# Program_Debug-Interface.net
KiCad netlist of a schematic drawn in Altium Designer
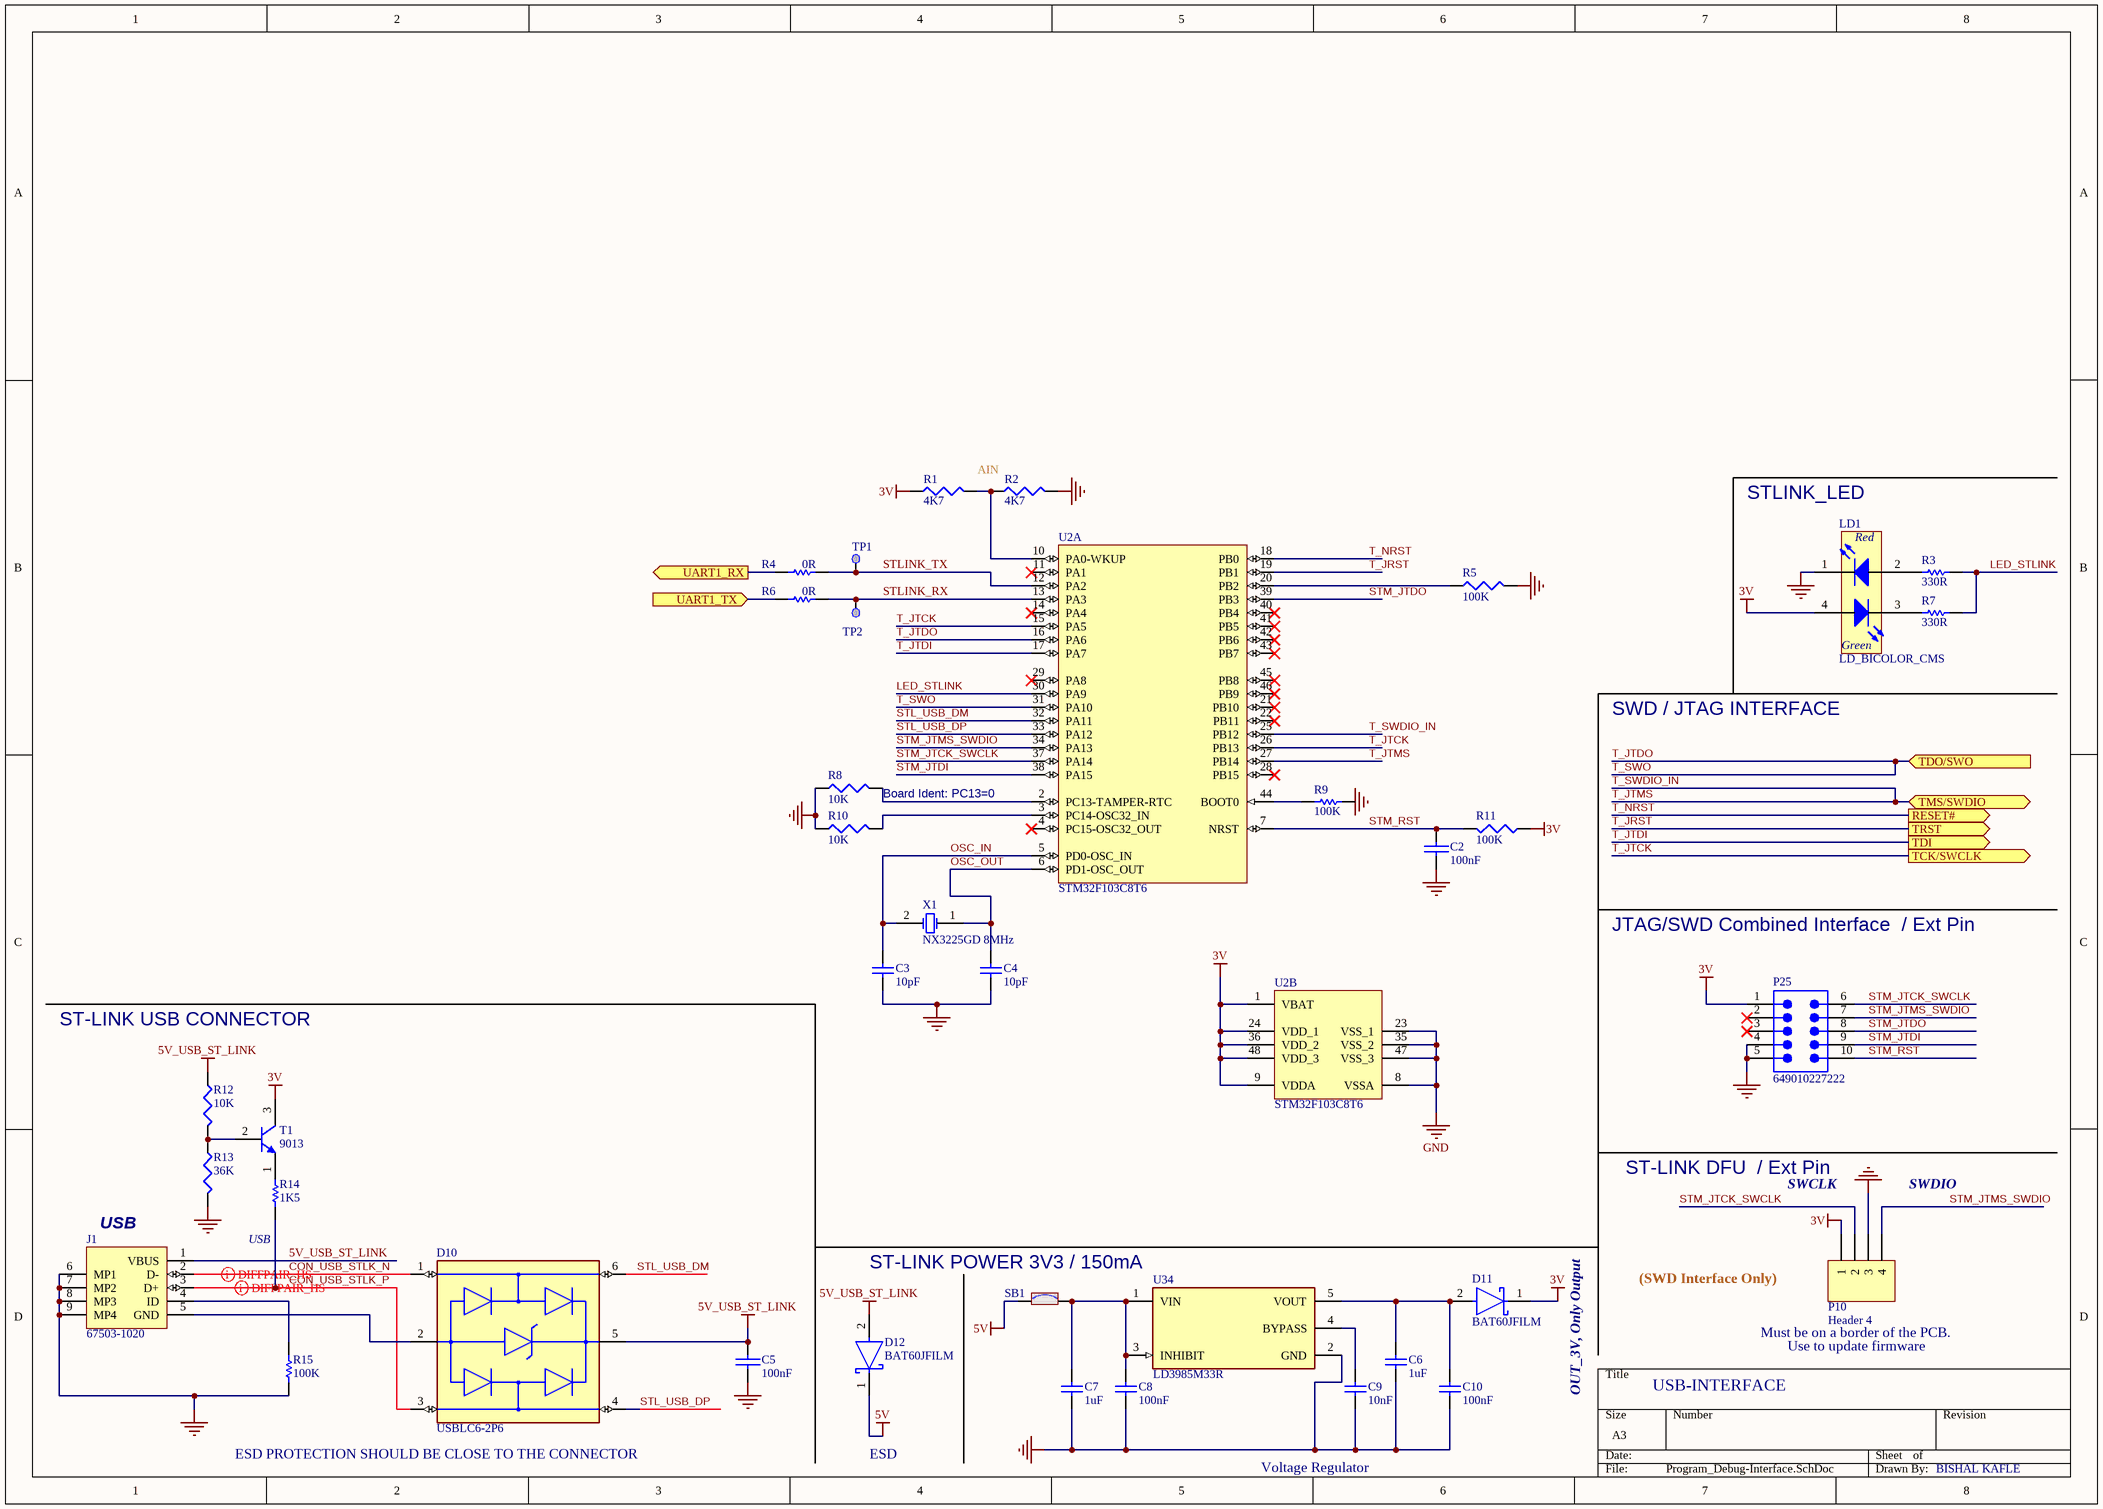
[diagram p0: Program_Debug-Interface.SchDoc]

(export (version "E")
  (design (tool "Eeschema 10.0.6"))
  (components
    (comp (ref "C2") (value "100nF") (footprint "0603C") (libsource (lib "") (part "CAP_1")))
    (comp (ref "C3")
      (value "10pF")
      (footprint "C0402")
      (description "Capacitor,10pF,50V,NPO,5%,0402")
      (fields
        (field (name "INTERNAL_PART_NUMBER") "MCD-00015")
        (field (name "MANUFACTURER_PART_NUMBER") "CC0402JRNPO9BN100")
        (field (name "PROVIDED_BY") "SUBCO")
      )
      (libsource (lib "MCD_PARTS_database") (part "Capacitor"))
    )
    (comp (ref "C4")
      (value "10pF")
      (footprint "C0402")
      (description "Capacitor,10pF,50V,NPO,5%,0402")
      (fields
        (field (name "INTERNAL_PART_NUMBER") "MCD-00015")
        (field (name "MANUFACTURER_PART_NUMBER") "CC0402JRNPO9BN100")
        (field (name "PROVIDED_BY") "SUBCO")
      )
      (libsource (lib "MCD_PARTS_database") (part "Capacitor"))
    )
    (comp (ref "C5")
      (value "100nF")
      (footprint "0603C")
      (description "Capacitor")
      (libsource (lib "*") (part "CAP"))
    )
    (comp (ref "C6")
      (value "1uF")
      (footprint "C0603")
      (description "Capacitor,1uF,6V3,X5R,10%,0603")
      (fields
        (field (name "INTERNAL_PART_NUMBER") "MCD-00238")
        (field (name "MANUFACTURER_PART_NUMBER") "CC0603KRX5R5BB105")
        (field (name "PROVIDED_BY") "SUBCO")
      )
      (libsource (lib "MCD_PARTS_database") (part "Capacitor"))
    )
    (comp (ref "C7")
      (value "1uF")
      (footprint "C0603")
      (description "Capacitor,1uF,6V3,X5R,10%,0603")
      (fields
        (field (name "INTERNAL_PART_NUMBER") "MCD-00238")
        (field (name "MANUFACTURER_PART_NUMBER") "CC0603KRX5R5BB105")
        (field (name "PROVIDED_BY") "SUBCO")
      )
      (libsource (lib "MCD_PARTS_database") (part "Capacitor"))
    )
    (comp (ref "C8")
      (value "100nF")
      (footprint "C0402")
      (description "Capacitor,100nF,16V,X7R,10%,0402")
      (fields
        (field (name "INTERNAL_PART_NUMBER") "MCD-00006")
        (field (name "MANUFACTURER_PART_NUMBER") "CC0402KRX7R7BB104")
        (field (name "PROVIDED_BY") "SUBCO")
      )
      (libsource (lib "MCD_PARTS_database") (part "Capacitor"))
    )
    (comp (ref "C9")
      (value "10nF")
      (footprint "C0402")
      (description "Capacitor,10nF,16V,X7R,10%,0402")
      (fields
        (field (name "INTERNAL_PART_NUMBER") "MCD-00011")
        (field (name "MANUFACTURER_PART_NUMBER") "CC0402KRX7R7BB103")
        (field (name "PROVIDED_BY") "SUBCO")
      )
      (libsource (lib "MCD_PARTS_database") (part "Capacitor"))
    )
    (comp (ref "C10")
      (value "100nF")
      (footprint "C0402")
      (description "Capacitor,100nF,16V,X7R,10%,0402")
      (fields
        (field (name "INTERNAL_PART_NUMBER") "MCD-00006")
        (field (name "MANUFACTURER_PART_NUMBER") "CC0402KRX7R7BB104")
        (field (name "PROVIDED_BY") "SUBCO")
      )
      (libsource (lib "MCD_PARTS_database") (part "Capacitor"))
    )
    (comp (ref "D10")
      (value "USBLC6-2P6")
      (footprint "FP-SOT-666-MFG")
      (description "TVS DIODE 5.25V 17V SOT666")
      (libsource (lib "Altium Content Vault") (part "c871e55f7e3243d341edbd671b98d92"))
    )
    (comp (ref "D11")
      (value "BAT60JFILM")
      (footprint "FP-BAT60JFILM-MFG")
      (description "DIODE SCHOTTKY 10V 3A SOD323")
      (libsource (lib "Altium Content Vault") (part "fefb30dabb5d097ae2f038500735429"))
    )
    (comp (ref "D12")
      (value "BAT60JFILM")
      (footprint "FP-BAT60JFILM-MFG")
      (description "DIODE SCHOTTKY 10V 3A SOD323")
      (libsource (lib "Altium Content Vault") (part "fefb30dabb5d097ae2f038500735429"))
    )
    (comp (ref "J1")
      (value "67503-1020")
      (footprint "MOLX-67503-1020_V")
      (description "USB, MINI, SMD, RA KME04-USBMU03A01")
      (fields (field (name "MANUFACTURER") "Molex"))
      (libsource (lib "esd_library") (part "MOLX-67503-1020"))
    )
    (comp (ref "LD1")
      (value "LD_BICOLOR_CMS")
      (footprint "LED_BI-GR_HSMF-A201-A00J1")
      (description "LED Bicolor")
      (fields
        (field (name "INTERNAL_PART_NUMBER") "MCD-00051")
        (field (name "MANUFACTURER_PART_NUMBER") "HSMF-A201-A00J1")
        (field (name "PROVIDED_BY") "SUBCO")
      )
      (libsource (lib "MCD_PARTS_database") (part "LD_BICOLOR_CMS"))
    )
    (comp (ref "P10")
      (value "Header 4")
      (footprint "HDR1X4")
      (description "Header, 4-Pin Male")
      (fields (field (name "MPN") "PEC04SFAN"))
      (libsource (lib "esd_library") (part "Header 4"))
    )
    (comp (ref "P25")
      (value "649010227222")
      (footprint "649010227222")
      (libsource (lib "Altium Content Vault") (part "Header_Male_2R_10P(A)"))
    )
    (comp (ref "R1") (value "4K7") (footprint "0603R") (libsource (lib "*") (part "RES1")))
    (comp (ref "R2") (value "4K7") (footprint "0603R") (libsource (lib "*") (part "RES1")))
    (comp (ref "R3")
      (value "330R")
      (footprint "R0402")
      (description "Resistor,330R,0402,1%,1/16W")
      (fields
        (field (name "INTERNAL_PART_NUMBER") "MCD-00062")
        (field (name "MANUFACTURER_PART_NUMBER") "RC0402FR-07330RL")
        (field (name "PROVIDED_BY") "SUBCO")
      )
      (libsource (lib "MCD_PARTS_database") (part "Resistor"))
    )
    (comp (ref "R4")
      (value "0R")
      (footprint "R0402")
      (description "Resistor,0R,0402,5%,1/16W")
      (fields
        (field (name "INTERNAL_PART_NUMBER") "MCD-00052")
        (field (name "MANUFACTURER_PART_NUMBER") "RC0402JR-070RL")
        (field (name "PROVIDED_BY") "SUBCO")
      )
      (libsource (lib "MCD_PARTS_database") (part "Resistor"))
    )
    (comp (ref "R5") (value "100K") (footprint "0603R") (libsource (lib "*") (part "RES1")))
    (comp (ref "R6")
      (value "0R")
      (footprint "R0402")
      (description "Resistor,0R,0402,5%,1/16W")
      (fields
        (field (name "INTERNAL_PART_NUMBER") "MCD-00052")
        (field (name "MANUFACTURER_PART_NUMBER") "RC0402JR-070RL")
        (field (name "PROVIDED_BY") "SUBCO")
      )
      (libsource (lib "MCD_PARTS_database") (part "Resistor"))
    )
    (comp (ref "R7")
      (value "330R")
      (footprint "R0402")
      (description "Resistor,330R,0402,1%,1/16W")
      (fields
        (field (name "INTERNAL_PART_NUMBER") "MCD-00062")
        (field (name "MANUFACTURER_PART_NUMBER") "RC0402FR-07330RL")
        (field (name "PROVIDED_BY") "SUBCO")
      )
      (libsource (lib "MCD_PARTS_database") (part "Resistor"))
    )
    (comp (ref "R8") (value "10K") (footprint "0603R") (libsource (lib "*") (part "R")))
    (comp (ref "R9")
      (value "100K")
      (footprint "R0402")
      (description "Resistor,100K,0402,1%,1/16W")
      (fields
        (field (name "INTERNAL_PART_NUMBER") "MCD-00059")
        (field (name "MANUFACTURER_PART_NUMBER") "RC0402FR-07100KL")
        (field (name "PROVIDED_BY") "SUBCO")
      )
      (libsource (lib "MCD_PARTS_database") (part "Resistor"))
    )
    (comp (ref "R10") (value "10K") (footprint "0603R") (libsource (lib "*") (part "R")))
    (comp (ref "R11") (value "100K") (footprint "0603R") (libsource (lib "*") (part "RES1")))
    (comp (ref "R12") (value "10K") (footprint "0603R") (libsource (lib "*") (part "R")))
    (comp (ref "R13") (value "36K") (footprint "0603R") (libsource (lib "*") (part "R")))
    (comp (ref "R14")
      (value "1K5")
      (footprint "0603R")
      (description "Resistor")
      (fields (field (name "PUBLISHER") "Altium Limited"))
      (libsource (lib "Miscellaneous Devices") (part "Res1"))
    )
    (comp (ref "R15")
      (value "100K")
      (footprint "R0402")
      (description "Resistor,100K,0402,1%,1/16W")
      (fields
        (field (name "INTERNAL_PART_NUMBER") "MCD-00059")
        (field (name "MANUFACTURER_PART_NUMBER") "RC0402FR-07100KL")
        (field (name "PROVIDED_BY") "SUBCO")
      )
      (libsource (lib "MCD_PARTS_database") (part "Resistor"))
    )
    (comp (ref "SB1")
      (value "~")
      (footprint "SOLDER-BRIDGE_R0603-0R")
      (description "Solder Bridge ON")
      (fields
        (field (name "INTERNAL_PART_NUMBER") "MCD-00071")
        (field (name "MANUFACTURER") "YAGEO")
        (field (name "PROVIDED_BY") "SUBCO")
      )
      (libsource (lib "MCD_PARTS_database") (part "SB_ON"))
    )
    (comp (ref "T1")
      (value "9013")
      (footprint "SOT23-213")
      (description "NPN Bipolar Transistor")
      (fields (field (name "PUBLISHER") "Altium Limited"))
      (libsource (lib "mb1045") (part "NPN"))
    )
    (comp (ref "TP1")
      (value "Test Point")
      (footprint "TP_SMD_1MM")
      (description "Test Point 1mm")
      (fields
        (field (name "INTERNAL_PART_NUMBER") "MCD-00074")
        (field (name "MANUFACTURER_PART_NUMBER") "n/a")
      )
      (libsource (lib "MCD_PARTS_database") (part "Test Point"))
    )
    (comp (ref "TP2")
      (value "Test Point")
      (footprint "TP_SMD_1MM")
      (description "Test Point 1mm")
      (fields
        (field (name "INTERNAL_PART_NUMBER") "MCD-00074")
        (field (name "MANUFACTURER_PART_NUMBER") "n/a")
      )
      (libsource (lib "") (part "Test Point_1"))
    )
    (comp (ref "U2")
      (value "STM32F103C8T6")
      (footprint "STM-LQFP48_L")
      (libsource (lib "Altium Content Vault") (part "MC-ARM-STM32F103X8_B-SQ48"))
    )
    (comp (ref "U34")
      (value "LD3985M33R")
      (footprint "FP-SOT23-5L-7049676-MFG")
      (libsource (lib "Altium Content Vault") (part "aba04f4e281572ab958dbcc456c8333"))
    )
    (comp (ref "X1")
      (value "NX3225GD 8MHz")
      (footprint "CRY_NX3225GD_2P")
      (description "Crystal 8Mhz, 8pF, -+50PPM, SMD")
      (fields
        (field (name "INTERNAL_PART_NUMBER") "MCD-00092")
        (field (name "MANUFACTURER_PART_NUMBER") "NX3225GD 8MHz EXS00A-CG04874")
        (field (name "PROVIDED_BY") "SUBCO")
      )
      (libsource (lib "MCD_PARTS_database") (part "XTAL_8M_NX3225GD"))
    )
  )
  (nets
    (net (code "1") (name "/CON_USB_STLK_N") (class "Default")
      (node (ref "D10") (pin "1") (pinfunction "I/O1_1") (pintype "bidirectional"))
      (node (ref "J1") (pin "2") (pinfunction "D-_2") (pintype "bidirectional"))
    )
    (net (code "2") (name "/CON_USB_STLK_P") (class "Default")
      (node (ref "D10") (pin "3") (pinfunction "I/O2_3") (pintype "bidirectional"))
      (node (ref "J1") (pin "3") (pinfunction "D+_3") (pintype "bidirectional"))
      (node (ref "R14") (pin "2") (pinfunction "2_2") (pintype "passive"))
    )
    (net (code "3") (name "/LED_STLINK") (class "Default")
      (node (ref "R3") (pin "2") (pinfunction "2_2") (pintype "passive"))
      (node (ref "R7") (pin "2") (pinfunction "2_2") (pintype "passive"))
      (node (ref "U2") (pin "30") (pinfunction "PA9_30") (pintype "bidirectional"))
    )
    (net (code "4") (name "/OSC_IN") (class "Default")
      (node (ref "C3") (pin "1") (pinfunction "1_1") (pintype "passive"))
      (node (ref "U2") (pin "5") (pinfunction "PD0-OSC_IN_5") (pintype "bidirectional"))
      (node (ref "X1") (pin "2") (pinfunction "OSC2_2") (pintype "passive"))
    )
    (net (code "5") (name "/OSC_OUT") (class "Default")
      (node (ref "C4") (pin "1") (pinfunction "1_1") (pintype "passive"))
      (node (ref "U2") (pin "6") (pinfunction "PD1-OSC_OUT_6") (pintype "bidirectional"))
      (node (ref "X1") (pin "1") (pinfunction "OSC1_1") (pintype "passive"))
    )
    (net (code "6") (name "/STLINK_RX") (class "Default")
      (node (ref "R6") (pin "2") (pinfunction "2_2") (pintype "passive"))
      (node (ref "TP2") (pin "1") (pinfunction "1_1") (pintype "passive"))
      (node (ref "U2") (pin "13") (pinfunction "PA3_13") (pintype "bidirectional"))
    )
    (net (code "7") (name "/STLINK_TX") (class "Default")
      (node (ref "R4") (pin "1") (pinfunction "1_1") (pintype "passive"))
      (node (ref "TP1") (pin "1") (pinfunction "1_1") (pintype "passive"))
      (node (ref "U2") (pin "12") (pinfunction "PA2_12") (pintype "bidirectional"))
    )
    (net (code "8") (name "/STL_USB_DM") (class "Default")
      (node (ref "D10") (pin "6") (pinfunction "I/O1_6") (pintype "bidirectional"))
      (node (ref "U2") (pin "32") (pinfunction "PA11_32") (pintype "bidirectional"))
    )
    (net (code "9") (name "/STL_USB_DP") (class "Default")
      (node (ref "D10") (pin "4") (pinfunction "I/O2_4") (pintype "bidirectional"))
      (node (ref "U2") (pin "33") (pinfunction "PA12_33") (pintype "bidirectional"))
    )
    (net (code "10") (name "/STM_JTCK_SWCLK") (class "Default")
      (node (ref "P10") (pin "2") (pinfunction "2_2") (pintype "passive"))
      (node (ref "P25") (pin "6") (pinfunction "6_6") (pintype "passive"))
      (node (ref "U2") (pin "37") (pinfunction "PA14_37") (pintype "bidirectional"))
    )
    (net (code "11") (name "/STM_JTDI") (class "Default")
      (node (ref "P25") (pin "9") (pinfunction "9_9") (pintype "passive"))
      (node (ref "U2") (pin "38") (pinfunction "PA15_38") (pintype "bidirectional"))
    )
    (net (code "12") (name "/STM_JTDO") (class "Default")
      (node (ref "P25") (pin "8") (pinfunction "8_8") (pintype "passive"))
      (node (ref "U2") (pin "39") (pinfunction "PB3_39") (pintype "bidirectional"))
    )
    (net (code "13") (name "/STM_JTMS_SWDIO") (class "Default")
      (node (ref "P10") (pin "4") (pinfunction "4_4") (pintype "passive"))
      (node (ref "P25") (pin "7") (pinfunction "7_7") (pintype "passive"))
      (node (ref "U2") (pin "34") (pinfunction "PA13_34") (pintype "bidirectional"))
    )
    (net (code "14") (name "/STM_RST") (class "Default")
      (node (ref "C2") (pin "2") (pinfunction "2_2") (pintype "passive"))
      (node (ref "P25") (pin "10") (pinfunction "10_10") (pintype "passive"))
      (node (ref "R11") (pin "1") (pinfunction "1_1") (pintype "passive"))
      (node (ref "U2") (pin "7") (pinfunction "NRST_7") (pintype "bidirectional"))
    )
    (net (code "15") (name "/T_JRST") (class "Default")
      (node (ref "U2") (pin "19") (pinfunction "PB1_19") (pintype "bidirectional"))
    )
    (net (code "16") (name "/T_JTCK") (class "Default")
      (node (ref "U2") (pin "15") (pinfunction "PA5_15") (pintype "bidirectional"))
      (node (ref "U2") (pin "26") (pinfunction "PB13_26") (pintype "bidirectional"))
    )
    (net (code "17") (name "/T_JTDI") (class "Default")
      (node (ref "U2") (pin "17") (pinfunction "PA7_17") (pintype "bidirectional"))
    )
    (net (code "18") (name "/T_JTDO") (class "Default")
      (node (ref "U2") (pin "16") (pinfunction "PA6_16") (pintype "bidirectional"))
      (node (ref "U2") (pin "31") (pinfunction "PA10_31") (pintype "bidirectional"))
    )
    (net (code "19") (name "/T_JTMS") (class "Default")
      (node (ref "U2") (pin "25") (pinfunction "PB12_25") (pintype "bidirectional"))
      (node (ref "U2") (pin "27") (pinfunction "PB14_27") (pintype "bidirectional"))
    )
    (net (code "20") (name "/T_NRST") (class "Default")
      (node (ref "U2") (pin "18") (pinfunction "PB0_18") (pintype "bidirectional"))
    )
    (net (code "21") (name "/UART1_RX") (class "Default")
      (node (ref "R4") (pin "2") (pinfunction "2_2") (pintype "passive"))
    )
    (net (code "22") (name "/UART1_TX") (class "Default")
      (node (ref "R6") (pin "1") (pinfunction "1_1") (pintype "passive"))
    )
    (net (code "23") (name "3V") (class "Default")
      (node (ref "D11") (pin "1") (pinfunction "K_1") (pintype "passive"))
      (node (ref "LD1") (pin "4") (pinfunction "YellowGreen_anode_4") (pintype "passive"))
      (node (ref "P10") (pin "1") (pinfunction "1_1") (pintype "passive"))
      (node (ref "P25") (pin "1") (pinfunction "1_1") (pintype "passive"))
      (node (ref "R1") (pin "1") (pinfunction "1_1") (pintype "passive"))
      (node (ref "R11") (pin "2") (pinfunction "2_2") (pintype "passive"))
      (node (ref "T1") (pin "3") (pinfunction "C_3") (pintype "passive"))
      (node (ref "U2") (pin "1") (pinfunction "VBAT_1") (pintype "power_in"))
      (node (ref "U2") (pin "24") (pinfunction "VDD_1_24") (pintype "power_in"))
      (node (ref "U2") (pin "36") (pinfunction "VDD_2_36") (pintype "power_in"))
      (node (ref "U2") (pin "48") (pinfunction "VDD_3_48") (pintype "power_in"))
      (node (ref "U2") (pin "9") (pinfunction "VDDA_9") (pintype "power_in"))
    )
    (net (code "24") (name "5V") (class "Default")
      (node (ref "D12") (pin "1") (pinfunction "K_1") (pintype "passive"))
      (node (ref "SB1") (pin "1") (pinfunction "1_1") (pintype "passive"))
    )
    (net (code "25") (name "5V_USB_ST_LINK") (class "Default")
      (node (ref "C5") (pin "1") (pinfunction "1_1") (pintype "passive"))
      (node (ref "D10") (pin "5") (pinfunction "VBUS_5") (pintype "power_in"))
      (node (ref "D12") (pin "2") (pinfunction "A_2") (pintype "passive"))
      (node (ref "J1") (pin "1") (pinfunction "VBUS_1") (pintype "power_in"))
      (node (ref "R12") (pin "1") (pinfunction "1_1") (pintype "passive"))
    )
    (net (code "26") (name "GND") (class "Default")
      (node (ref "C10") (pin "1") (pinfunction "1_1") (pintype "passive"))
      (node (ref "C2") (pin "1") (pinfunction "1_1") (pintype "passive"))
      (node (ref "C3") (pin "2") (pinfunction "2_2") (pintype "passive"))
      (node (ref "C4") (pin "2") (pinfunction "2_2") (pintype "passive"))
      (node (ref "C5") (pin "2") (pinfunction "2_2") (pintype "passive"))
      (node (ref "C6") (pin "1") (pinfunction "1_1") (pintype "passive"))
      (node (ref "C7") (pin "2") (pinfunction "2_2") (pintype "passive"))
      (node (ref "C8") (pin "1") (pinfunction "1_1") (pintype "passive"))
      (node (ref "C9") (pin "1") (pinfunction "1_1") (pintype "passive"))
      (node (ref "J1") (pin "6") (pinfunction "MP1_6") (pintype "passive"))
      (node (ref "J1") (pin "7") (pinfunction "MP2_7") (pintype "passive"))
      (node (ref "J1") (pin "8") (pinfunction "MP3_8") (pintype "passive"))
      (node (ref "J1") (pin "9") (pinfunction "MP4_9") (pintype "passive"))
      (node (ref "LD1") (pin "1") (pinfunction "RED_cathode_1") (pintype "passive"))
      (node (ref "P10") (pin "3") (pinfunction "3_3") (pintype "passive"))
      (node (ref "P25") (pin "4") (pinfunction "4_4") (pintype "passive"))
      (node (ref "P25") (pin "5") (pinfunction "5_5") (pintype "passive"))
      (node (ref "R10") (pin "1") (pinfunction "1_1") (pintype "passive"))
      (node (ref "R13") (pin "2") (pinfunction "2_2") (pintype "passive"))
      (node (ref "R15") (pin "1") (pinfunction "1_1") (pintype "passive"))
      (node (ref "R2") (pin "2") (pinfunction "2_2") (pintype "passive"))
      (node (ref "R5") (pin "2") (pinfunction "2_2") (pintype "passive"))
      (node (ref "R8") (pin "1") (pinfunction "1_1") (pintype "passive"))
      (node (ref "U2") (pin "23") (pinfunction "VSS_1_23") (pintype "power_in"))
      (node (ref "U2") (pin "35") (pinfunction "VSS_2_35") (pintype "power_in"))
      (node (ref "U2") (pin "47") (pinfunction "VSS_3_47") (pintype "power_in"))
      (node (ref "U2") (pin "8") (pinfunction "VSSA_8") (pintype "power_in"))
      (node (ref "U34") (pin "2") (pinfunction "GND_2") (pintype "power_in"))
    )
    (net (code "27") (name "Net-(D10-GND)") (class "Default")
      (node (ref "D10") (pin "2") (pinfunction "GND_2") (pintype "power_in"))
      (node (ref "J1") (pin "5") (pinfunction "GND_5") (pintype "power_in"))
    )
    (net (code "28") (name "Net-(D11-A)") (class "Default")
      (node (ref "C10") (pin "2") (pinfunction "2_2") (pintype "passive"))
      (node (ref "C6") (pin "2") (pinfunction "2_2") (pintype "passive"))
      (node (ref "D11") (pin "2") (pinfunction "A_2") (pintype "passive"))
      (node (ref "U34") (pin "5") (pinfunction "VOUT_5") (pintype "passive"))
    )
    (net (code "29") (name "Net-(J1-ID)") (class "Default")
      (node (ref "J1") (pin "4") (pinfunction "ID_4") (pintype "passive"))
      (node (ref "R15") (pin "2") (pinfunction "2_2") (pintype "passive"))
    )
    (net (code "30") (name "Net-(LD1-Red_anode)") (class "Default")
      (node (ref "LD1") (pin "2") (pinfunction "Red_anode_2") (pintype "passive"))
      (node (ref "R3") (pin "1") (pinfunction "1_1") (pintype "passive"))
    )
    (net (code "31") (name "Net-(LD1-YellowGreen_cathode)") (class "Default")
      (node (ref "LD1") (pin "3") (pinfunction "YellowGreen_cathode_3") (pintype "passive"))
      (node (ref "R7") (pin "1") (pinfunction "1_1") (pintype "passive"))
    )
    (net (code "32") (name "Net-(T1-B)") (class "Default")
      (node (ref "R12") (pin "2") (pinfunction "2_2") (pintype "passive"))
      (node (ref "R13") (pin "1") (pinfunction "1_1") (pintype "passive"))
      (node (ref "T1") (pin "2") (pinfunction "B_2") (pintype "passive"))
    )
    (net (code "33") (name "Net-(U2A-BOOT0)") (class "Default")
      (node (ref "R9") (pin "2") (pinfunction "2_2") (pintype "passive"))
      (node (ref "U2") (pin "44") (pinfunction "BOOT0_44") (pintype "input"))
    )
    (net (code "34") (name "Net-(U2A-PA0-WKUP)") (class "Default")
      (node (ref "R1") (pin "2") (pinfunction "2_2") (pintype "passive"))
      (node (ref "R2") (pin "1") (pinfunction "1_1") (pintype "passive"))
      (node (ref "U2") (pin "10") (pinfunction "PA0-WKUP_10") (pintype "bidirectional"))
    )
    (net (code "35") (name "Net-(U2A-PB2)") (class "Default")
      (node (ref "R5") (pin "1") (pinfunction "1_1") (pintype "passive"))
      (node (ref "U2") (pin "20") (pinfunction "PB2_20") (pintype "bidirectional"))
    )
    (net (code "36") (name "Net-(U2A-PC13-TAMPER-RTC)") (class "Default")
      (node (ref "R8") (pin "2") (pinfunction "2_2") (pintype "passive"))
      (node (ref "U2") (pin "2") (pinfunction "PC13-TAMPER-RTC_2") (pintype "bidirectional"))
    )
    (net (code "37") (name "Net-(U2A-PC14-OSC32_IN)") (class "Default")
      (node (ref "R10") (pin "2") (pinfunction "2_2") (pintype "passive"))
      (node (ref "U2") (pin "3") (pinfunction "PC14-OSC32_IN_3") (pintype "bidirectional"))
    )
    (net (code "38") (name "Net-(U34-BYPASS)") (class "Default")
      (node (ref "C9") (pin "2") (pinfunction "2_2") (pintype "passive"))
      (node (ref "U34") (pin "4") (pinfunction "BYPASS_4") (pintype "passive"))
    )
    (net (code "39") (name "Net-(U34-INHIBIT)") (class "Default")
      (node (ref "C7") (pin "1") (pinfunction "1_1") (pintype "passive"))
      (node (ref "C8") (pin "2") (pinfunction "2_2") (pintype "passive"))
      (node (ref "SB1") (pin "2") (pinfunction "2_2") (pintype "passive"))
      (node (ref "U34") (pin "1") (pinfunction "VIN_1") (pintype "power_in"))
      (node (ref "U34") (pin "3") (pinfunction "INHIBIT_3") (pintype "input"))
    )
    (net (code "40") (name "unconnected-(P25-Pad2)") (class "Default")
      (node (ref "P25") (pin "2") (pinfunction "2_2") (pintype "passive+no_connect"))
    )
    (net (code "41") (name "unconnected-(P25-Pad3)") (class "Default")
      (node (ref "P25") (pin "3") (pinfunction "3_3") (pintype "passive+no_connect"))
    )
    (net (code "42") (name "unconnected-(R9-Pad1)") (class "Default")
      (node (ref "R9") (pin "1") (pinfunction "1_1") (pintype "passive"))
    )
    (net (code "43") (name "unconnected-(R14-Pad1)") (class "Default")
      (node (ref "R14") (pin "1") (pinfunction "1_1") (pintype "passive"))
    )
    (net (code "44") (name "unconnected-(T1-E-Pad1)") (class "Default")
      (node (ref "T1") (pin "1") (pinfunction "E_1") (pintype "passive"))
    )
    (net (code "45") (name "unconnected-(U2A-PA1-Pad11)") (class "Default")
      (node (ref "U2") (pin "11") (pinfunction "PA1_11") (pintype "bidirectional+no_connect"))
    )
    (net (code "46") (name "unconnected-(U2A-PA4-Pad14)") (class "Default")
      (node (ref "U2") (pin "14") (pinfunction "PA4_14") (pintype "bidirectional+no_connect"))
    )
    (net (code "47") (name "unconnected-(U2A-PA8-Pad29)") (class "Default")
      (node (ref "U2") (pin "29") (pinfunction "PA8_29") (pintype "bidirectional+no_connect"))
    )
    (net (code "48") (name "unconnected-(U2A-PB4-Pad40)") (class "Default")
      (node (ref "U2") (pin "40") (pinfunction "PB4_40") (pintype "bidirectional+no_connect"))
    )
    (net (code "49") (name "unconnected-(U2A-PB5-Pad41)") (class "Default")
      (node (ref "U2") (pin "41") (pinfunction "PB5_41") (pintype "bidirectional+no_connect"))
    )
    (net (code "50") (name "unconnected-(U2A-PB6-Pad42)") (class "Default")
      (node (ref "U2") (pin "42") (pinfunction "PB6_42") (pintype "bidirectional+no_connect"))
    )
    (net (code "51") (name "unconnected-(U2A-PB7-Pad43)") (class "Default")
      (node (ref "U2") (pin "43") (pinfunction "PB7_43") (pintype "bidirectional+no_connect"))
    )
    (net (code "52") (name "unconnected-(U2A-PB8-Pad45)") (class "Default")
      (node (ref "U2") (pin "45") (pinfunction "PB8_45") (pintype "bidirectional+no_connect"))
    )
    (net (code "53") (name "unconnected-(U2A-PB9-Pad46)") (class "Default")
      (node (ref "U2") (pin "46") (pinfunction "PB9_46") (pintype "bidirectional+no_connect"))
    )
    (net (code "54") (name "unconnected-(U2A-PB10-Pad21)") (class "Default")
      (node (ref "U2") (pin "21") (pinfunction "PB10_21") (pintype "bidirectional+no_connect"))
    )
    (net (code "55") (name "unconnected-(U2A-PB11-Pad22)") (class "Default")
      (node (ref "U2") (pin "22") (pinfunction "PB11_22") (pintype "bidirectional+no_connect"))
    )
    (net (code "56") (name "unconnected-(U2A-PB15-Pad28)") (class "Default")
      (node (ref "U2") (pin "28") (pinfunction "PB15_28") (pintype "bidirectional+no_connect"))
    )
    (net (code "57") (name "unconnected-(U2A-PC15-OSC32_OUT-Pad4)") (class "Default")
      (node (ref "U2") (pin "4") (pinfunction "PC15-OSC32_OUT_4") (pintype "bidirectional+no_connect"))
    )
  )
)
